# sheet1.net
KiCad netlist of a schematic drawn in Altium Designer
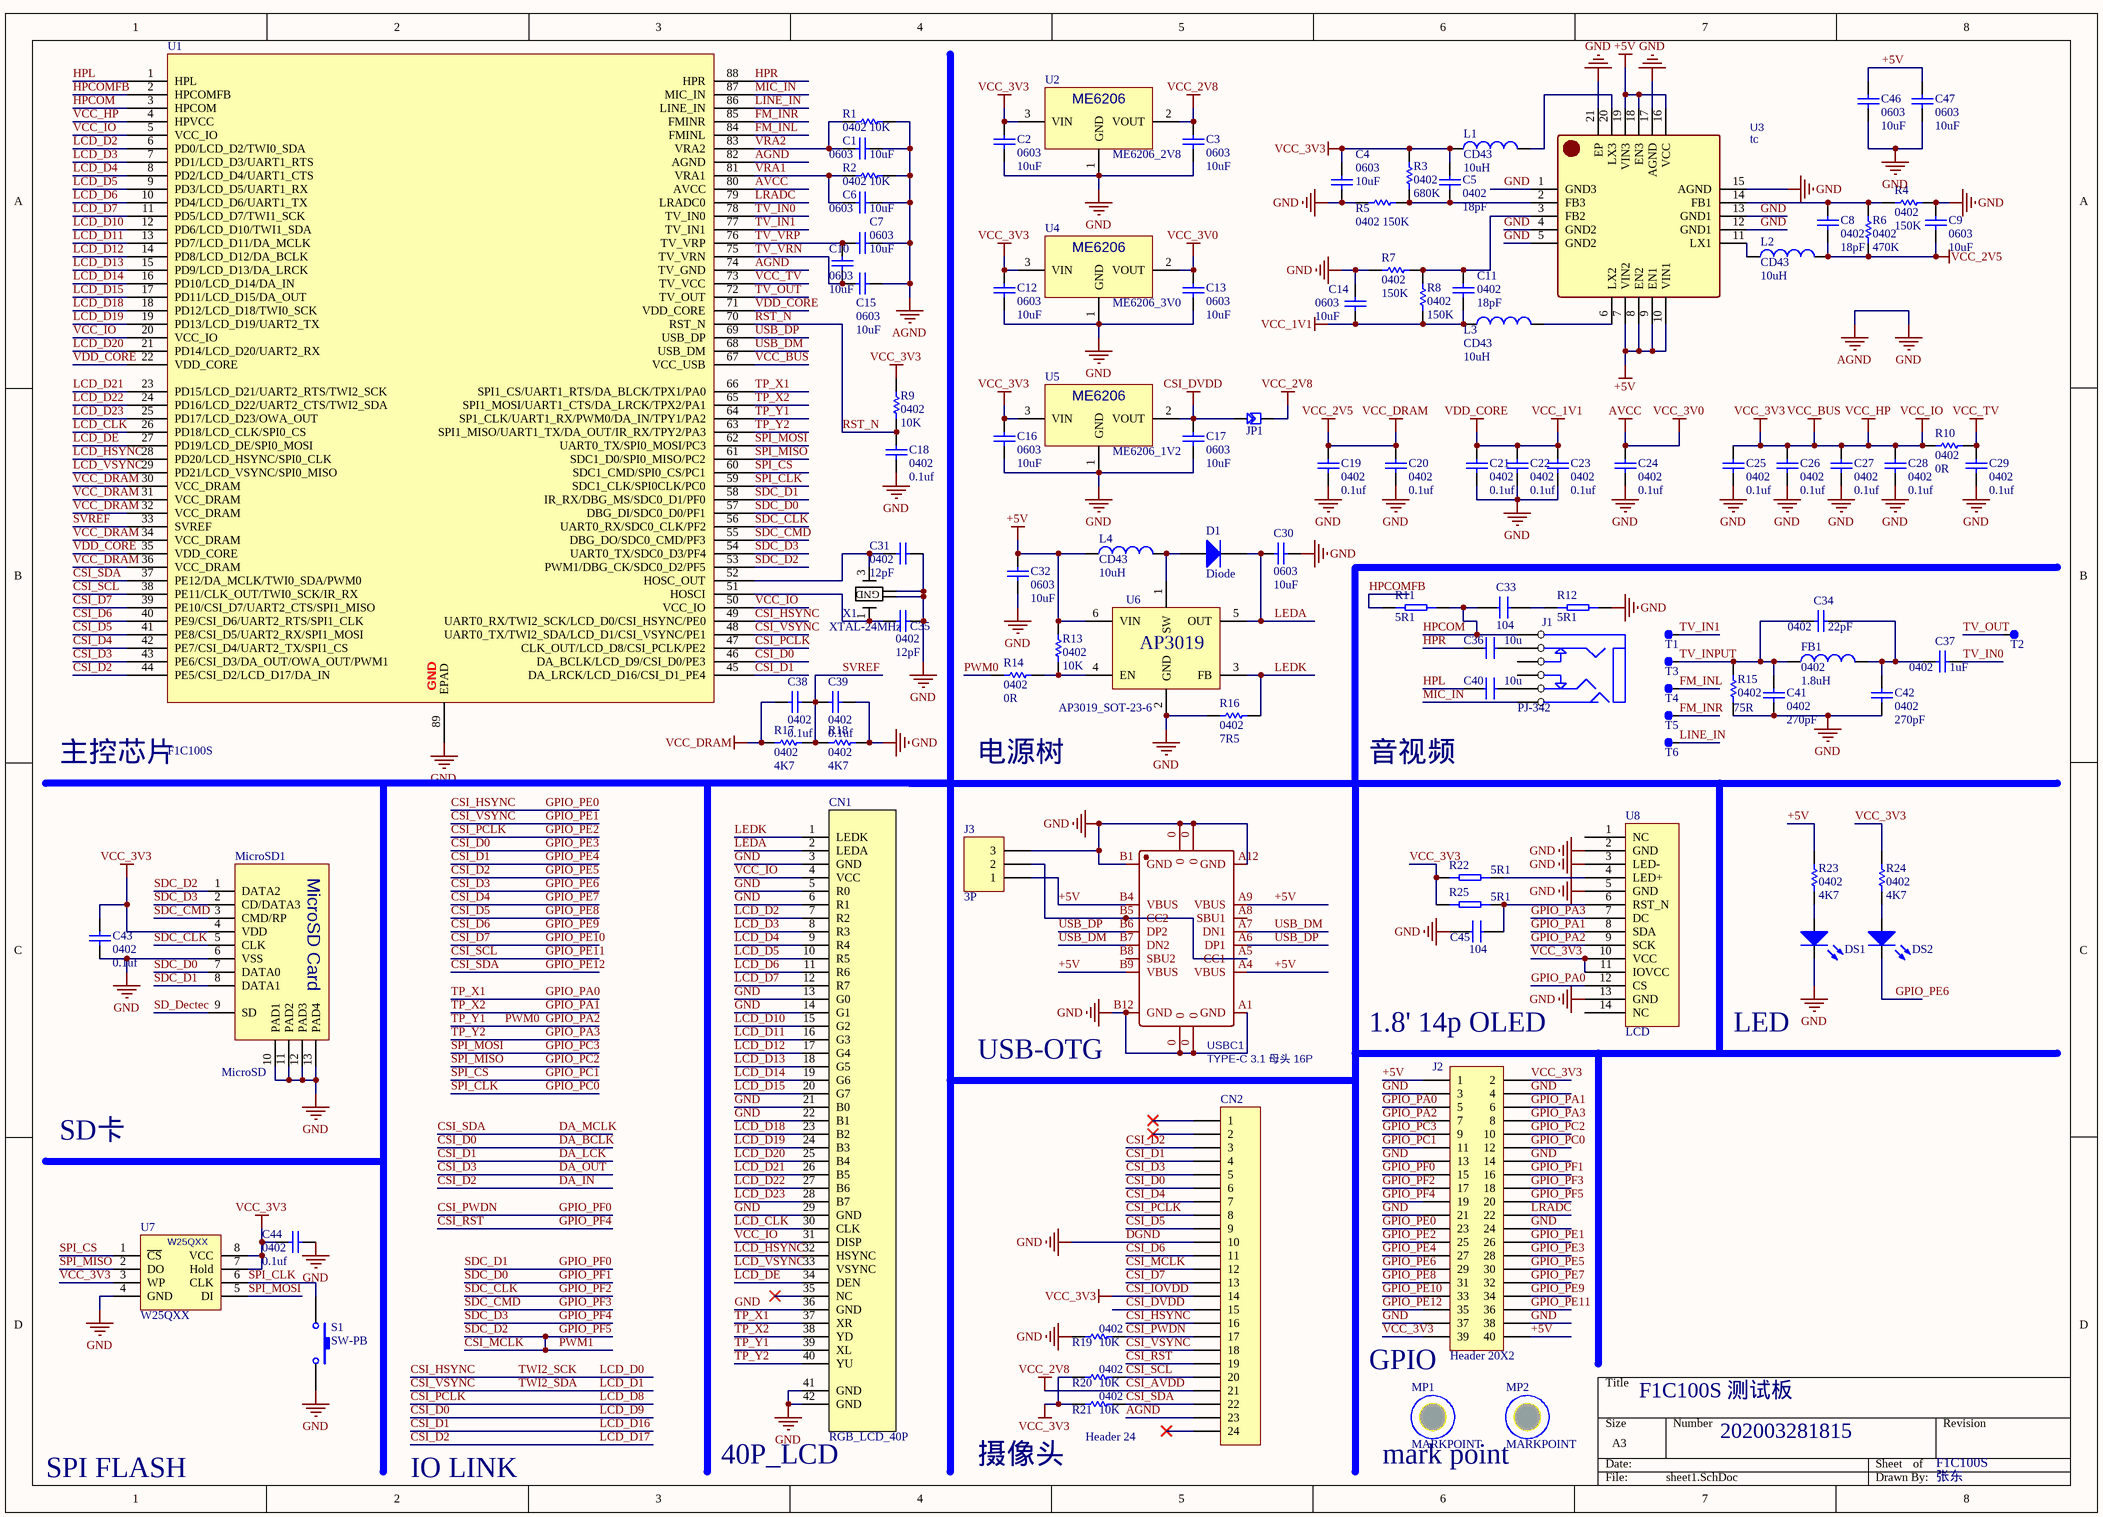
[diagram p0: sheet1.SchDoc]

(export (version "E")
  (design (tool "Eeschema 10.0.6"))
  (components
    (comp (ref "C1")
      (value "0603")
      (footprint "0603AC")
      (description "Capacitor")
      (fields (field (name "ALTIUM_VALUE") "10uF") (field (name "PUBLISHER") "Altium Limited"))
      (libsource (lib "Miscellaneous Devices") (part "Cap"))
    )
    (comp (ref "C2")
      (value "0603")
      (footprint "0603AC")
      (description "Capacitor")
      (fields (field (name "ALTIUM_VALUE") "10uF") (field (name "PUBLISHER") "Altium Limited"))
      (libsource (lib "Miscellaneous Devices") (part "Cap"))
    )
    (comp (ref "C3")
      (value "0603")
      (footprint "0603AC")
      (description "Capacitor")
      (fields (field (name "ALTIUM_VALUE") "10uF") (field (name "PUBLISHER") "Altium Limited"))
      (libsource (lib "Miscellaneous Devices") (part "Cap"))
    )
    (comp (ref "C4")
      (value "0603")
      (footprint "0603AC")
      (description "Capacitor")
      (fields (field (name "ALTIUM_VALUE") "10uF") (field (name "PUBLISHER") "Altium Limited"))
      (libsource (lib "Miscellaneous Devices") (part "Cap"))
    )
    (comp (ref "C5")
      (value "0402")
      (footprint "0402AC")
      (description "Capacitor")
      (fields (field (name "ALTIUM_VALUE") "18pF") (field (name "PUBLISHER") "Altium Limited"))
      (libsource (lib "Miscellaneous Devices") (part "Cap"))
    )
    (comp (ref "C6")
      (value "0603")
      (footprint "0603AC")
      (description "Capacitor")
      (fields (field (name "ALTIUM_VALUE") "10uF") (field (name "PUBLISHER") "Altium Limited"))
      (libsource (lib "Miscellaneous Devices") (part "Cap"))
    )
    (comp (ref "C7")
      (value "0603")
      (footprint "0603AC")
      (description "Capacitor")
      (fields (field (name "ALTIUM_VALUE") "10uF") (field (name "PUBLISHER") "Altium Limited"))
      (libsource (lib "Miscellaneous Devices") (part "Cap"))
    )
    (comp (ref "C8")
      (value "0402")
      (footprint "0402AC")
      (description "Capacitor")
      (fields (field (name "ALTIUM_VALUE") "18pF") (field (name "PUBLISHER") "Altium Limited"))
      (libsource (lib "Miscellaneous Devices") (part "Cap"))
    )
    (comp (ref "C9")
      (value "0603")
      (footprint "0603AC")
      (description "Capacitor")
      (fields (field (name "ALTIUM_VALUE") "10uF") (field (name "PUBLISHER") "Altium Limited"))
      (libsource (lib "Miscellaneous Devices") (part "Cap"))
    )
    (comp (ref "C10")
      (value "0603")
      (footprint "0603AC")
      (description "Capacitor")
      (fields (field (name "ALTIUM_VALUE") "10uF") (field (name "PUBLISHER") "Altium Limited"))
      (libsource (lib "Miscellaneous Devices") (part "Cap"))
    )
    (comp (ref "C11")
      (value "0402")
      (footprint "0402AC")
      (description "Capacitor")
      (fields (field (name "ALTIUM_VALUE") "18pF") (field (name "PUBLISHER") "Altium Limited"))
      (libsource (lib "Miscellaneous Devices") (part "Cap"))
    )
    (comp (ref "C12")
      (value "0603")
      (footprint "0603AC")
      (description "Capacitor")
      (fields (field (name "ALTIUM_VALUE") "10uF") (field (name "PUBLISHER") "Altium Limited"))
      (libsource (lib "Miscellaneous Devices") (part "Cap"))
    )
    (comp (ref "C13")
      (value "0603")
      (footprint "0603AC")
      (description "Capacitor")
      (fields (field (name "ALTIUM_VALUE") "10uF") (field (name "PUBLISHER") "Altium Limited"))
      (libsource (lib "Miscellaneous Devices") (part "Cap"))
    )
    (comp (ref "C14")
      (value "0603")
      (footprint "0603AC")
      (description "Capacitor")
      (fields (field (name "ALTIUM_VALUE") "10uF") (field (name "PUBLISHER") "Altium Limited"))
      (libsource (lib "Miscellaneous Devices") (part "Cap"))
    )
    (comp (ref "C15")
      (value "0603")
      (footprint "0603AC")
      (description "Capacitor")
      (fields (field (name "ALTIUM_VALUE") "10uF") (field (name "PUBLISHER") "Altium Limited"))
      (libsource (lib "Miscellaneous Devices") (part "Cap"))
    )
    (comp (ref "C16")
      (value "0603")
      (footprint "0603AC")
      (description "Capacitor")
      (fields (field (name "ALTIUM_VALUE") "10uF") (field (name "PUBLISHER") "Altium Limited"))
      (libsource (lib "Miscellaneous Devices") (part "Cap"))
    )
    (comp (ref "C17")
      (value "0603")
      (footprint "0603AC")
      (description "Capacitor")
      (fields (field (name "ALTIUM_VALUE") "10uF") (field (name "PUBLISHER") "Altium Limited"))
      (libsource (lib "Miscellaneous Devices") (part "Cap"))
    )
    (comp (ref "C18")
      (value "0402")
      (footprint "0402AC")
      (description "Capacitor")
      (fields (field (name "ALTIUM_VALUE") "0.1uf") (field (name "PUBLISHER") "Altium Limited"))
      (libsource (lib "Miscellaneous Devices") (part "Cap"))
    )
    (comp (ref "C19")
      (value "0402")
      (footprint "0402AC")
      (description "Capacitor")
      (fields (field (name "ALTIUM_VALUE") "0.1uf") (field (name "PUBLISHER") "Altium Limited"))
      (libsource (lib "Miscellaneous Devices") (part "Cap"))
    )
    (comp (ref "C20")
      (value "0402")
      (footprint "0402AC")
      (description "Capacitor")
      (fields (field (name "ALTIUM_VALUE") "0.1uf") (field (name "PUBLISHER") "Altium Limited"))
      (libsource (lib "Miscellaneous Devices") (part "Cap"))
    )
    (comp (ref "C21")
      (value "0402")
      (footprint "0402AC")
      (description "Capacitor")
      (fields (field (name "ALTIUM_VALUE") "0.1uf") (field (name "PUBLISHER") "Altium Limited"))
      (libsource (lib "Miscellaneous Devices") (part "Cap"))
    )
    (comp (ref "C22")
      (value "0402")
      (footprint "0402AC")
      (description "Capacitor")
      (fields (field (name "ALTIUM_VALUE") "0.1uf") (field (name "PUBLISHER") "Altium Limited"))
      (libsource (lib "Miscellaneous Devices") (part "Cap"))
    )
    (comp (ref "C23")
      (value "0402")
      (footprint "0402AC")
      (description "Capacitor")
      (fields (field (name "ALTIUM_VALUE") "0.1uf") (field (name "PUBLISHER") "Altium Limited"))
      (libsource (lib "Miscellaneous Devices") (part "Cap"))
    )
    (comp (ref "C24")
      (value "0402")
      (footprint "0402AC")
      (description "Capacitor")
      (fields (field (name "ALTIUM_VALUE") "0.1uf") (field (name "PUBLISHER") "Altium Limited"))
      (libsource (lib "Miscellaneous Devices") (part "Cap"))
    )
    (comp (ref "C25")
      (value "0402")
      (footprint "0402AC")
      (description "Capacitor")
      (fields (field (name "ALTIUM_VALUE") "0.1uf") (field (name "PUBLISHER") "Altium Limited"))
      (libsource (lib "Miscellaneous Devices") (part "Cap"))
    )
    (comp (ref "C26")
      (value "0402")
      (footprint "0402AC")
      (description "Capacitor")
      (fields (field (name "ALTIUM_VALUE") "0.1uf") (field (name "PUBLISHER") "Altium Limited"))
      (libsource (lib "Miscellaneous Devices") (part "Cap"))
    )
    (comp (ref "C27")
      (value "0402")
      (footprint "0402AC")
      (description "Capacitor")
      (fields (field (name "ALTIUM_VALUE") "0.1uf") (field (name "PUBLISHER") "Altium Limited"))
      (libsource (lib "Miscellaneous Devices") (part "Cap"))
    )
    (comp (ref "C28")
      (value "0402")
      (footprint "0402AC")
      (description "Capacitor")
      (fields (field (name "ALTIUM_VALUE") "0.1uf") (field (name "PUBLISHER") "Altium Limited"))
      (libsource (lib "Miscellaneous Devices") (part "Cap"))
    )
    (comp (ref "C29")
      (value "0402")
      (footprint "0402AC")
      (description "Capacitor")
      (fields (field (name "ALTIUM_VALUE") "0.1uf") (field (name "PUBLISHER") "Altium Limited"))
      (libsource (lib "Miscellaneous Devices") (part "Cap"))
    )
    (comp (ref "C30")
      (value "0603")
      (footprint "0603AC")
      (description "Capacitor")
      (fields (field (name "ALTIUM_VALUE") "10uF") (field (name "PUBLISHER") "Altium Limited"))
      (libsource (lib "Miscellaneous Devices") (part "Cap"))
    )
    (comp (ref "C31")
      (value "0402")
      (footprint "0402AC")
      (description "Capacitor")
      (fields (field (name "ALTIUM_VALUE") "12pF") (field (name "PUBLISHER") "Altium Limited"))
      (libsource (lib "Miscellaneous Devices") (part "Cap"))
    )
    (comp (ref "C32")
      (value "0603")
      (footprint "0603AC")
      (description "Capacitor")
      (fields (field (name "ALTIUM_VALUE") "10uF") (field (name "PUBLISHER") "Altium Limited"))
      (libsource (lib "Miscellaneous Devices") (part "Cap"))
    )
    (comp (ref "C33")
      (value "104")
      (footprint "0402C")
      (description "SMD-CAP")
      (libsource (lib "lpi-nano-dock") (part "CAP"))
    )
    (comp (ref "C34")
      (value "0402")
      (footprint "0402AC")
      (description "Capacitor")
      (fields (field (name "ALTIUM_VALUE") "22pF") (field (name "PUBLISHER") "Altium Limited"))
      (libsource (lib "Miscellaneous Devices") (part "Cap"))
    )
    (comp (ref "C35")
      (value "0402")
      (footprint "0402AC")
      (description "Capacitor")
      (fields (field (name "ALTIUM_VALUE") "12pF") (field (name "PUBLISHER") "Altium Limited"))
      (libsource (lib "Miscellaneous Devices") (part "Cap"))
    )
    (comp (ref "C36")
      (value "10u")
      (footprint "0402C")
      (description "SMD-CAP")
      (libsource (lib "lpi-nano-dock") (part "CAP"))
    )
    (comp (ref "C37")
      (value "0402")
      (footprint "0402AC")
      (description "Capacitor")
      (fields (field (name "ALTIUM_VALUE") "1uF") (field (name "PUBLISHER") "Altium Limited"))
      (libsource (lib "Miscellaneous Devices") (part "Cap"))
    )
    (comp (ref "C38")
      (value "0402")
      (footprint "0402AC")
      (description "Capacitor")
      (fields (field (name "ALTIUM_VALUE") "0.1uf") (field (name "PUBLISHER") "Altium Limited"))
      (libsource (lib "Miscellaneous Devices") (part "Cap"))
    )
    (comp (ref "C39")
      (value "0402")
      (footprint "0402AC")
      (description "Capacitor")
      (fields (field (name "ALTIUM_VALUE") "0.1uf") (field (name "PUBLISHER") "Altium Limited"))
      (libsource (lib "Miscellaneous Devices") (part "Cap"))
    )
    (comp (ref "C40")
      (value "10u")
      (footprint "0402C")
      (description "SMD-CAP")
      (libsource (lib "lpi-nano-dock") (part "CAP"))
    )
    (comp (ref "C41")
      (value "0402")
      (footprint "0402AC")
      (description "Capacitor")
      (fields (field (name "ALTIUM_VALUE") "270pF") (field (name "PUBLISHER") "Altium Limited"))
      (libsource (lib "Miscellaneous Devices") (part "Cap"))
    )
    (comp (ref "C42")
      (value "0402")
      (footprint "0402AC")
      (description "Capacitor")
      (fields (field (name "ALTIUM_VALUE") "270pF") (field (name "PUBLISHER") "Altium Limited"))
      (libsource (lib "Miscellaneous Devices") (part "Cap"))
    )
    (comp (ref "C43")
      (value "0402")
      (footprint "0402AC")
      (description "Capacitor")
      (fields (field (name "ALTIUM_VALUE") "0.1uf") (field (name "PUBLISHER") "Altium Limited"))
      (libsource (lib "Miscellaneous Devices") (part "Cap"))
    )
    (comp (ref "C44")
      (value "0402")
      (footprint "0402AC")
      (description "Capacitor")
      (fields (field (name "ALTIUM_VALUE") "0.1uf") (field (name "PUBLISHER") "Altium Limited"))
      (libsource (lib "Miscellaneous Devices") (part "Cap"))
    )
    (comp (ref "C45")
      (value "104")
      (footprint "0402C")
      (description "SMD-CAP")
      (libsource (lib "lpi-nano-dock") (part "CAP"))
    )
    (comp (ref "C46")
      (value "0603")
      (footprint "0603AC")
      (description "Capacitor")
      (fields (field (name "ALTIUM_VALUE") "10uF") (field (name "PUBLISHER") "Altium Limited"))
      (libsource (lib "Miscellaneous Devices") (part "Cap"))
    )
    (comp (ref "C47")
      (value "0603")
      (footprint "0603AC")
      (description "Capacitor")
      (fields (field (name "ALTIUM_VALUE") "10uF") (field (name "PUBLISHER") "Altium Limited"))
      (libsource (lib "Miscellaneous Devices") (part "Cap"))
    )
    (comp (ref "CN1")
      (value "RGB_LCD_40P")
      (footprint "FH19C-40S-0.5SH")
      (libsource (lib "7426SCH") (part "RGB_LCD_40P"))
    )
    (comp (ref "CN2")
      (value "Header 24")
      (footprint "FH19C-24S-0.5SH")
      (description "Header, 24-Pin")
      (fields (field (name "PUBLISHER") "Altium Limited"))
      (libsource (lib "Miscellaneous Connectors") (part "Header 24"))
    )
    (comp (ref "D1")
      (value "Diode")
      (footprint "SOD123")
      (description "Default Diode")
      (fields (field (name "PUBLISHER") "Altium Limited"))
      (libsource (lib "Miscellaneous Devices") (part "Diode"))
    )
    (comp (ref "DS1") (value "LED") (footprint "LED 0805B") (libsource (lib "QT") (part "LED")))
    (comp (ref "DS2") (value "LED") (footprint "LED 0805B") (libsource (lib "QT") (part "LED")))
    (comp (ref "FB1")
      (value "0402")
      (footprint "0402AR")
      (description "CD43")
      (fields (field (name "ALTIUM_VALUE") "1.8uH") (field (name "PUBLISHER") "Altium Limited"))
      (libsource (lib "Miscellaneous Devices") (part "Inductor"))
    )
    (comp (ref "J1") (value "PJ-342") (footprint "PJ-342") (libsource (lib "lpi-nano-dock") (part "PJ-342")))
    (comp (ref "J2")
      (value "Header 20X2")
      (footprint "HDR2X20")
      (description "Header, 20-Pin, Dual row")
      (fields (field (name "PUBLISHER") "Altium Limited"))
      (libsource (lib "Miscellaneous Connectors") (part "Header 20X2"))
    )
    (comp (ref "J3") (value "3P") (footprint "3P") (libsource (lib "常用元件库") (part "3P")))
    (comp (ref "JP1") (value "SW-PAD-2") (footprint "SW-PAD-2") (libsource (lib "7426SCH") (part "SW-PAD-2")))
    (comp (ref "L1")
      (value "CD43")
      (footprint "2520")
      (fields (field (name "ALTIUM_VALUE") "10uH") (field (name "PUBLISHER") "Altium Limited"))
      (libsource (lib "Miscellaneous Devices") (part "Inductor"))
    )
    (comp (ref "L2")
      (value "CD43")
      (footprint "2520")
      (fields (field (name "ALTIUM_VALUE") "10uH") (field (name "PUBLISHER") "Altium Limited"))
      (libsource (lib "Miscellaneous Devices") (part "Inductor"))
    )
    (comp (ref "L3")
      (value "CD43")
      (footprint "2520")
      (fields (field (name "ALTIUM_VALUE") "10uH") (field (name "PUBLISHER") "Altium Limited"))
      (libsource (lib "Miscellaneous Devices") (part "Inductor"))
    )
    (comp (ref "L4")
      (value "CD43")
      (footprint "2520")
      (fields (field (name "ALTIUM_VALUE") "10uH") (field (name "PUBLISHER") "Altium Limited"))
      (libsource (lib "Miscellaneous Devices") (part "Inductor"))
    )
    (comp (ref "MicroSD1")
      (value "MicroSD")
      (footprint "MicroSD")
      (libsource (lib "7426SCH") (part "MicroSD"))
    )
    (comp (ref "MP1")
      (value "MARKPOINT")
      (footprint "MARKPOINT")
      (libsource (lib "7426SCH") (part "MARKPOINT"))
    )
    (comp (ref "MP2")
      (value "MARKPOINT")
      (footprint "MARKPOINT")
      (libsource (lib "7426SCH") (part "MARKPOINT"))
    )
    (comp (ref "R1")
      (value "0402")
      (footprint "0402AR")
      (description "Resistor")
      (fields (field (name "ALTIUM_VALUE") "10K") (field (name "PUBLISHER") "Altium Limited"))
      (libsource (lib "Miscellaneous Devices") (part "Res1"))
    )
    (comp (ref "R2")
      (value "0402")
      (footprint "0402AR")
      (description "Resistor")
      (fields (field (name "ALTIUM_VALUE") "10K") (field (name "PUBLISHER") "Altium Limited"))
      (libsource (lib "Miscellaneous Devices") (part "Res1"))
    )
    (comp (ref "R3")
      (value "0402")
      (footprint "0402AR")
      (fields (field (name "ALTIUM_VALUE") "680K") (field (name "PUBLISHER") "Altium Limited"))
      (libsource (lib "Miscellaneous Devices") (part "Res1"))
    )
    (comp (ref "R4")
      (value "0402")
      (footprint "0402AR")
      (description "Resistor")
      (fields (field (name "ALTIUM_VALUE") "150K") (field (name "PUBLISHER") "Altium Limited"))
      (libsource (lib "Miscellaneous Devices") (part "Res1"))
    )
    (comp (ref "R5")
      (value "0402")
      (footprint "0402AR")
      (description "Resistor")
      (fields (field (name "ALTIUM_VALUE") "150K") (field (name "PUBLISHER") "Altium Limited"))
      (libsource (lib "Miscellaneous Devices") (part "Res1"))
    )
    (comp (ref "R6")
      (value "0402")
      (footprint "0402AR")
      (fields (field (name "ALTIUM_VALUE") "470K") (field (name "PUBLISHER") "Altium Limited"))
      (libsource (lib "Miscellaneous Devices") (part "Res1"))
    )
    (comp (ref "R7")
      (value "0402")
      (footprint "0402AR")
      (fields (field (name "ALTIUM_VALUE") "150K") (field (name "PUBLISHER") "Altium Limited"))
      (libsource (lib "Miscellaneous Devices") (part "Res1"))
    )
    (comp (ref "R8")
      (value "0402")
      (footprint "0402AR")
      (fields (field (name "ALTIUM_VALUE") "150K") (field (name "PUBLISHER") "Altium Limited"))
      (libsource (lib "Miscellaneous Devices") (part "Res1"))
    )
    (comp (ref "R9")
      (value "0402")
      (footprint "0402AR")
      (fields (field (name "ALTIUM_VALUE") "10K") (field (name "PUBLISHER") "Altium Limited"))
      (libsource (lib "Miscellaneous Devices") (part "Res1"))
    )
    (comp (ref "R10")
      (value "0402")
      (footprint "0402AR")
      (fields (field (name "ALTIUM_VALUE") "0R") (field (name "PUBLISHER") "Altium Limited"))
      (libsource (lib "Miscellaneous Devices") (part "Res1"))
    )
    (comp (ref "R11") (value "5R1") (footprint "0402R") (libsource (lib "lpi-nano-dock") (part "R")))
    (comp (ref "R12") (value "5R1") (footprint "0402R") (libsource (lib "lpi-nano-dock") (part "R")))
    (comp (ref "R13")
      (value "0402")
      (footprint "0402AR")
      (fields (field (name "ALTIUM_VALUE") "10K") (field (name "PUBLISHER") "Altium Limited"))
      (libsource (lib "Miscellaneous Devices") (part "Res1"))
    )
    (comp (ref "R14")
      (value "0402")
      (footprint "0402AR")
      (fields (field (name "ALTIUM_VALUE") "0R") (field (name "PUBLISHER") "Altium Limited"))
      (libsource (lib "Miscellaneous Devices") (part "Res1"))
    )
    (comp (ref "R15")
      (value "0402")
      (footprint "0402AR")
      (description "Resistor")
      (fields (field (name "ALTIUM_VALUE") "75R") (field (name "PUBLISHER") "Altium Limited"))
      (libsource (lib "Miscellaneous Devices") (part "Res1"))
    )
    (comp (ref "R16")
      (value "0402")
      (footprint "0402AR")
      (fields (field (name "ALTIUM_VALUE") "7R5") (field (name "PUBLISHER") "Altium Limited"))
      (libsource (lib "Miscellaneous Devices") (part "Res1"))
    )
    (comp (ref "R17")
      (value "0402")
      (footprint "0402AR")
      (fields (field (name "ALTIUM_VALUE") "4K7") (field (name "PUBLISHER") "Altium Limited"))
      (libsource (lib "Miscellaneous Devices") (part "Res1"))
    )
    (comp (ref "R18")
      (value "0402")
      (footprint "0402AR")
      (fields (field (name "ALTIUM_VALUE") "4K7") (field (name "PUBLISHER") "Altium Limited"))
      (libsource (lib "Miscellaneous Devices") (part "Res1"))
    )
    (comp (ref "R19")
      (value "0402")
      (footprint "0402AR")
      (fields (field (name "ALTIUM_VALUE") "10K") (field (name "PUBLISHER") "Altium Limited"))
      (libsource (lib "Miscellaneous Devices") (part "Res1"))
    )
    (comp (ref "R20")
      (value "0402")
      (footprint "0402AR")
      (fields (field (name "ALTIUM_VALUE") "10K") (field (name "PUBLISHER") "Altium Limited"))
      (libsource (lib "Miscellaneous Devices") (part "Res1"))
    )
    (comp (ref "R21")
      (value "0402")
      (footprint "0402AR")
      (fields (field (name "ALTIUM_VALUE") "10K") (field (name "PUBLISHER") "Altium Limited"))
      (libsource (lib "Miscellaneous Devices") (part "Res1"))
    )
    (comp (ref "R22") (value "5R1") (footprint "0402R") (libsource (lib "lpi-nano-dock") (part "R")))
    (comp (ref "R23")
      (value "0402")
      (footprint "0402AR")
      (fields (field (name "ALTIUM_VALUE") "4K7") (field (name "PUBLISHER") "Altium Limited"))
      (libsource (lib "PineapplePi-F1") (part "Res1"))
    )
    (comp (ref "R24")
      (value "0402")
      (footprint "0402AR")
      (fields (field (name "ALTIUM_VALUE") "4K7") (field (name "PUBLISHER") "Altium Limited"))
      (libsource (lib "PineapplePi-F1") (part "Res1"))
    )
    (comp (ref "R25") (value "5R1") (footprint "0402R") (libsource (lib "lpi-nano-dock") (part "R")))
    (comp (ref "S1")
      (value "SW-PB")
      (footprint "SW-SMD1")
      (description "Switch")
      (fields (field (name "PUBLISHER") "Altium Limited"))
      (libsource (lib "Miscellaneous Devices") (part "SW-PB"))
    )
    (comp (ref "T1") (value "1 测试点") (footprint "SIP1-1*1") (libsource (lib "常用元件库") (part "1 测试点")))
    (comp (ref "T2") (value "1 测试点") (footprint "SIP1-1*1") (libsource (lib "常用元件库") (part "1 测试点")))
    (comp (ref "T3") (value "1 测试点") (footprint "SIP1-1*1") (libsource (lib "常用元件库") (part "1 测试点")))
    (comp (ref "T4") (value "1 测试点") (footprint "SIP1-1*1") (libsource (lib "常用元件库") (part "1 测试点")))
    (comp (ref "T5") (value "1 测试点") (footprint "SIP1-1*1") (libsource (lib "常用元件库") (part "1 测试点")))
    (comp (ref "T6") (value "1 测试点") (footprint "SIP1-1*1") (libsource (lib "常用元件库") (part "1 测试点")))
    (comp (ref "U1") (value "F1C100S") (footprint "QFN88-10X10") (libsource (lib "F1C100S") (part "F1C100S")))
    (comp (ref "U2") (value "ME6206_2V8") (footprint "SOT-23") (libsource (lib "IC") (part "ME6206")))
    (comp (ref "U3")
      (value "tc")
      (footprint "QFN20-3x3-0.4")
      (fields (field (name "BOM_MANUFACTURER PART") "EA3036QDR") (field (name "BOM_SUPPLIER PART") "C111587"))
      (libsource (lib "IC") (part "EA3036QDR"))
    )
    (comp (ref "U4") (value "ME6206_3V0") (footprint "SOT-23") (libsource (lib "IC") (part "ME6206")))
    (comp (ref "U5") (value "ME6206_1V2") (footprint "SOT-23") (libsource (lib "IC") (part "ME6206")))
    (comp (ref "U6") (value "AP3019_SOT-23-6") (footprint "SOT23-6") (libsource (lib "IC") (part "AP3019")))
    (comp (ref "U7") (value "W25QXX") (footprint "SO-8M") (libsource (lib "IC") (part "W25QXX")))
    (comp (ref "U8")
      (value "LCD")
      (footprint "LCD_SPI_14P_sim")
      (libsource (lib "lpi-nano-dock") (part "LCD_SPI_14P"))
    )
    (comp (ref "USBC1")
      (value "TYPE-C 3.1 母头 16P")
      (footprint "TYPE-C-USB-12")
      (libsource (lib "Interface") (part "TYPE-C 3.1 母头 16P"))
    )
    (comp (ref "X1")
      (value "XTAL-24MHz")
      (footprint "XTAL-3225")
      (libsource (lib "7426SCH") (part "XTAL-SMD"))
    )
  )
  (nets
    (net (code "1") (name "+5V") (class "Default")
      (node (ref "C32") (pin "2") (pinfunction "2_2") (pintype "passive"))
      (node (ref "C46") (pin "2") (pinfunction "2_2") (pintype "passive"))
      (node (ref "C47") (pin "2") (pinfunction "2_2") (pintype "passive"))
      (node (ref "J2") (pin "1") (pinfunction "1_1") (pintype "passive"))
      (node (ref "J2") (pin "40") (pinfunction "40_40") (pintype "passive"))
      (node (ref "J3") (pin "1") (pinfunction "1_1") (pintype "passive"))
      (node (ref "L4") (pin "1") (pinfunction "1_1") (pintype "passive"))
      (node (ref "R13") (pin "1") (pinfunction "1_1") (pintype "passive"))
      (node (ref "R23") (pin "2") (pinfunction "2_2") (pintype "passive"))
      (node (ref "U3") (pin "10") (pinfunction "VIN1_10") (pintype "passive"))
      (node (ref "U3") (pin "16") (pinfunction "VCC_16") (pintype "passive"))
      (node (ref "U3") (pin "18") (pinfunction "EN3_18") (pintype "passive"))
      (node (ref "U3") (pin "19") (pinfunction "VIN3_19") (pintype "passive"))
      (node (ref "U3") (pin "7") (pinfunction "VIN2_7") (pintype "passive"))
      (node (ref "U3") (pin "8") (pinfunction "EN2_8") (pintype "passive"))
      (node (ref "U3") (pin "9") (pinfunction "EN1_9") (pintype "passive"))
      (node (ref "U6") (pin "6") (pinfunction "VIN_6") (pintype "passive"))
      (node (ref "USBC1") (pin "A4") (pinfunction "VBUS_A4") (pintype "passive"))
      (node (ref "USBC1") (pin "A9") (pinfunction "VBUS_A9") (pintype "passive"))
      (node (ref "USBC1") (pin "B4") (pinfunction "VBUS_B4") (pintype "passive"))
      (node (ref "USBC1") (pin "B9") (pinfunction "VBUS_B9") (pintype "passive"))
    )
    (net (code "2") (name "/CSI_D0") (class "Default")
      (node (ref "CN2") (pin "6") (pinfunction "6_6") (pintype "passive"))
      (node (ref "J2") (pin "28") (pinfunction "28_28") (pintype "passive"))
      (node (ref "U1") (pin "46") (pinfunction "DA_BCLK/LCD_D9/CSI_D0/PE3_46") (pintype "passive"))
    )
    (net (code "3") (name "/CSI_D1") (class "Default")
      (node (ref "CN2") (pin "4") (pinfunction "4_4") (pintype "passive"))
      (node (ref "J2") (pin "27") (pinfunction "27_27") (pintype "passive"))
      (node (ref "U1") (pin "45") (pinfunction "DA_LRCK/LCD_D16/CSI_D1_PE4_45") (pintype "passive"))
    )
    (net (code "4") (name "/CSI_D2") (class "Default")
      (node (ref "CN2") (pin "3") (pinfunction "3_3") (pintype "passive"))
      (node (ref "J2") (pin "30") (pinfunction "30_30") (pintype "passive"))
      (node (ref "U1") (pin "44") (pinfunction "PE5/CSI_D2/LCD_D17/DA_IN_44") (pintype "passive"))
    )
    (net (code "5") (name "/CSI_D3") (class "Default")
      (node (ref "CN2") (pin "5") (pinfunction "5_5") (pintype "passive"))
      (node (ref "DS2") (pin "2") (pinfunction "K_2") (pintype "passive"))
      (node (ref "J2") (pin "29") (pinfunction "29_29") (pintype "passive"))
      (node (ref "U1") (pin "43") (pinfunction "PE6/CSI_D3/DA_OUT/OWA_OUT/PWM1_43") (pintype "passive"))
    )
    (net (code "6") (name "/CSI_D4") (class "Default")
      (node (ref "CN2") (pin "7") (pinfunction "7_7") (pintype "passive"))
      (node (ref "J2") (pin "32") (pinfunction "32_32") (pintype "passive"))
      (node (ref "U1") (pin "42") (pinfunction "PE7/CSI_D4/UART2_TX/SPI1_CS_42") (pintype "passive"))
    )
    (net (code "7") (name "/CSI_D5") (class "Default")
      (node (ref "CN2") (pin "9") (pinfunction "9_9") (pintype "passive"))
      (node (ref "J2") (pin "31") (pinfunction "31_31") (pintype "passive"))
      (node (ref "U1") (pin "41") (pinfunction "PE8/CSI_D5/UART2_RX/SPI1_MOSI_41") (pintype "passive"))
    )
    (net (code "8") (name "/CSI_D6") (class "Default")
      (node (ref "CN2") (pin "11") (pinfunction "11_11") (pintype "passive"))
      (node (ref "J2") (pin "34") (pinfunction "34_34") (pintype "passive"))
      (node (ref "U1") (pin "40") (pinfunction "PE9/CSI_D6/UART2_RTS/SPI1_CLK_40") (pintype "passive"))
    )
    (net (code "9") (name "/CSI_D7") (class "Default")
      (node (ref "CN2") (pin "13") (pinfunction "13_13") (pintype "passive"))
      (node (ref "J2") (pin "33") (pinfunction "33_33") (pintype "passive"))
      (node (ref "U1") (pin "39") (pinfunction "PE10/CSI_D7/UART2_CTS/SPI1_MISO_39") (pintype "passive"))
    )
    (net (code "10") (name "/CSI_HSYNC") (class "Default")
      (node (ref "CN2") (pin "16") (pinfunction "16_16") (pintype "passive"))
      (node (ref "J2") (pin "23") (pinfunction "23_23") (pintype "passive"))
      (node (ref "U1") (pin "49") (pinfunction "UART0_RX/TWI2_SCK/LCD_D0/CSI_HSYNC/PE0_49") (pintype "passive"))
    )
    (net (code "11") (name "/CSI_MCLK") (class "Default")
      (node (ref "CN2") (pin "12") (pinfunction "12_12") (pintype "passive"))
      (node (ref "J2") (pin "20") (pinfunction "20_20") (pintype "passive"))
      (node (ref "MicroSD1") (pin "1") (pinfunction "DATA2_1") (pintype "power_in"))
      (node (ref "U1") (pin "53") (pinfunction "PWM1/DBG_CK/SDC0_D2/PF5_53") (pintype "passive"))
    )
    (net (code "12") (name "/CSI_PCLK") (class "Default")
      (node (ref "CN2") (pin "8") (pinfunction "8_8") (pintype "passive"))
      (node (ref "J2") (pin "25") (pinfunction "25_25") (pintype "passive"))
      (node (ref "U1") (pin "47") (pinfunction "CLK_OUT/LCD_D8/CSI_PCLK/PE2_47") (pintype "passive"))
    )
    (net (code "13") (name "/CSI_PWDN") (class "Default")
      (node (ref "CN2") (pin "17") (pinfunction "17_17") (pintype "passive"))
      (node (ref "J2") (pin "15") (pinfunction "15_15") (pintype "passive"))
      (node (ref "MicroSD1") (pin "8") (pinfunction "DATA1_8") (pintype "power_in"))
      (node (ref "R19") (pin "2") (pinfunction "2_2") (pintype "passive"))
      (node (ref "U1") (pin "58") (pinfunction "IR_RX/DBG_MS/SDC0_D1/PF0_58") (pintype "passive"))
    )
    (net (code "14") (name "/CSI_RST") (class "Default")
      (node (ref "CN2") (pin "19") (pinfunction "19_19") (pintype "passive"))
      (node (ref "J2") (pin "19") (pinfunction "19_19") (pintype "passive"))
      (node (ref "MicroSD1") (pin "2") (pinfunction "CD/DATA3_2") (pintype "power_in"))
      (node (ref "U1") (pin "54") (pinfunction "UART0_TX/SDC0_D3/PF4_54") (pintype "passive"))
    )
    (net (code "15") (name "/CSI_SCL") (class "Default")
      (node (ref "CN2") (pin "20") (pinfunction "20_20") (pintype "passive"))
      (node (ref "J2") (pin "36") (pinfunction "36_36") (pintype "passive"))
      (node (ref "R20") (pin "1") (pinfunction "1_1") (pintype "passive"))
      (node (ref "U1") (pin "38") (pinfunction "PE11/CLK_OUT/TWI0_SCK/IR_RX_38") (pintype "passive"))
    )
    (net (code "16") (name "/CSI_SDA") (class "Default")
      (node (ref "CN2") (pin "22") (pinfunction "22_22") (pintype "passive"))
      (node (ref "J2") (pin "35") (pinfunction "35_35") (pintype "passive"))
      (node (ref "R21") (pin "1") (pinfunction "1_1") (pintype "passive"))
      (node (ref "U1") (pin "37") (pinfunction "PE12/DA_MCLK/TWI0_SDA/PWM0_37") (pintype "passive"))
    )
    (net (code "17") (name "/CSI_VSYNC") (class "Default")
      (node (ref "CN2") (pin "18") (pinfunction "18_18") (pintype "passive"))
      (node (ref "J2") (pin "26") (pinfunction "26_26") (pintype "passive"))
      (node (ref "U1") (pin "48") (pinfunction "UART0_TX/TWI2_SDA/LCD_D1/CSI_VSYNC/PE1_48") (pintype "passive"))
    )
    (net (code "18") (name "/FM_INL") (class "Default")
      (node (ref "T4") (pin "1") (pintype "passive"))
      (node (ref "U1") (pin "84") (pinfunction "FMINL_84") (pintype "passive"))
    )
    (net (code "19") (name "/FM_INR") (class "Default")
      (node (ref "T5") (pin "1") (pintype "passive"))
      (node (ref "U1") (pin "85") (pinfunction "FMINR_85") (pintype "passive"))
    )
    (net (code "20") (name "/GPIO_PA0") (class "Default")
      (node (ref "CN1") (pin "37") (pinfunction "XR_37") (pintype "passive"))
      (node (ref "J2") (pin "5") (pinfunction "5_5") (pintype "passive"))
      (node (ref "U1") (pin "66") (pinfunction "SPI1_CS/UART1_RTS/DA_BLCK/TPX1/PA0_66") (pintype "passive"))
      (node (ref "U8") (pin "12") (pinfunction "CS_12") (pintype "passive"))
    )
    (net (code "21") (name "/GPIO_PA1") (class "Default")
      (node (ref "CN1") (pin "38") (pinfunction "YD_38") (pintype "passive"))
      (node (ref "J2") (pin "6") (pinfunction "6_6") (pintype "passive"))
      (node (ref "U1") (pin "65") (pinfunction "SPI1_MOSI/UART1_CTS/DA_LRCK/TPX2/PA1_65") (pintype "passive"))
      (node (ref "U8") (pin "8") (pinfunction "SDA_8") (pintype "passive"))
    )
    (net (code "22") (name "/GPIO_PA2") (class "Default")
      (node (ref "CN1") (pin "39") (pinfunction "XL_39") (pintype "passive"))
      (node (ref "J2") (pin "7") (pinfunction "7_7") (pintype "passive"))
      (node (ref "R14") (pin "1") (pinfunction "1_1") (pintype "passive"))
      (node (ref "U1") (pin "64") (pinfunction "SP1_CLK/UART1_RX/PWM0/DA_IN/TPY1/PA2_64") (pintype "passive"))
      (node (ref "U8") (pin "9") (pinfunction "SCK_9") (pintype "passive"))
    )
    (net (code "23") (name "/GPIO_PA3") (class "Default")
      (node (ref "CN1") (pin "40") (pinfunction "YU_40") (pintype "passive"))
      (node (ref "J2") (pin "8") (pinfunction "8_8") (pintype "passive"))
      (node (ref "U1") (pin "63") (pinfunction "SPI1_MISO/UART1_TX/DA_OUT/IR_RX/TPY2/PA3_63") (pintype "passive"))
      (node (ref "U8") (pin "7") (pinfunction "DC_7") (pintype "passive"))
    )
    (net (code "24") (name "/GPIO_PC0") (class "Default")
      (node (ref "J2") (pin "12") (pinfunction "12_12") (pintype "passive"))
      (node (ref "S1") (pin "1") (pinfunction "1_1") (pintype "passive"))
      (node (ref "U1") (pin "59") (pinfunction "SDC1_CLK/SPI0CLK/PC0_59") (pintype "passive"))
      (node (ref "U7") (pin "6") (pinfunction "CLK_6") (pintype "power_in"))
    )
    (net (code "25") (name "/GPIO_PC1") (class "Default")
      (node (ref "J2") (pin "11") (pinfunction "11_11") (pintype "passive"))
      (node (ref "U1") (pin "60") (pinfunction "SDC1_CMD/SPI0_CS/PC1_60") (pintype "passive"))
      (node (ref "U7") (pin "1") (pinfunction "~{CS}_1") (pintype "power_in"))
    )
    (net (code "26") (name "/GPIO_PC2") (class "Default")
      (node (ref "J2") (pin "10") (pinfunction "10_10") (pintype "passive"))
      (node (ref "U1") (pin "61") (pinfunction "SDC1_D0/SPI0_MISO/PC2_61") (pintype "passive"))
      (node (ref "U7") (pin "2") (pinfunction "DO_2") (pintype "power_in"))
    )
    (net (code "27") (name "/GPIO_PC3") (class "Default")
      (node (ref "J2") (pin "9") (pinfunction "9_9") (pintype "passive"))
      (node (ref "U1") (pin "62") (pinfunction "UART0_TX/SPI0_MOSI/PC3_62") (pintype "passive"))
      (node (ref "U7") (pin "5") (pinfunction "DI_5") (pintype "power_in"))
    )
    (net (code "28") (name "/GPIO_PF1") (class "Default")
      (node (ref "J2") (pin "16") (pinfunction "16_16") (pintype "passive"))
      (node (ref "MicroSD1") (pin "7") (pinfunction "DATA0_7") (pintype "power_in"))
      (node (ref "U1") (pin "57") (pinfunction "DBG_DI/SDC0_D0/PF1_57") (pintype "passive"))
    )
    (net (code "29") (name "/GPIO_PF2") (class "Default")
      (node (ref "J2") (pin "17") (pinfunction "17_17") (pintype "passive"))
      (node (ref "MicroSD1") (pin "5") (pinfunction "CLK_5") (pintype "power_in"))
      (node (ref "U1") (pin "56") (pinfunction "UART0_RX/SDC0_CLK/PF2_56") (pintype "passive"))
    )
    (net (code "30") (name "/GPIO_PF3") (class "Default")
      (node (ref "J2") (pin "18") (pinfunction "18_18") (pintype "passive"))
      (node (ref "MicroSD1") (pin "3") (pinfunction "CMD/RP_3") (pintype "power_in"))
      (node (ref "U1") (pin "55") (pinfunction "DBG_DO/SDC0_CMD/PF3_55") (pintype "passive"))
    )
    (net (code "31") (name "/HPCOM") (class "Default")
      (node (ref "C33") (pin "1") (pinfunction "1_1") (pintype "passive"))
      (node (ref "J1") (pin "2") (pinfunction "MIC_2") (pintype "passive"))
      (node (ref "R11") (pin "2") (pinfunction "2_2") (pintype "passive"))
      (node (ref "U1") (pin "3") (pinfunction "HPCOM_3") (pintype "passive"))
    )
    (net (code "32") (name "/HPCOMFB") (class "Default")
      (node (ref "R11") (pin "1") (pinfunction "1_1") (pintype "passive"))
      (node (ref "U1") (pin "2") (pinfunction "HPCOMFB_2") (pintype "passive"))
    )
    (net (code "33") (name "/HPL") (class "Default")
      (node (ref "C40") (pin "2") (pinfunction "2_2") (pintype "passive"))
      (node (ref "U1") (pin "1") (pinfunction "HPL_1") (pintype "passive"))
    )
    (net (code "34") (name "/HPR") (class "Default")
      (node (ref "C36") (pin "1") (pinfunction "1_1") (pintype "passive"))
      (node (ref "U1") (pin "88") (pinfunction "HPR_88") (pintype "passive"))
    )
    (net (code "35") (name "/LCD_CLK") (class "Default")
      (node (ref "CN1") (pin "30") (pinfunction "CLK_30") (pintype "passive"))
      (node (ref "U1") (pin "26") (pinfunction "PD18/LCD_CLK/SPI0_CS_26") (pintype "passive"))
    )
    (net (code "36") (name "/LCD_D2") (class "Default")
      (node (ref "CN1") (pin "7") (pinfunction "R2_7") (pintype "passive"))
      (node (ref "U1") (pin "6") (pinfunction "PD0/LCD_D2/TWI0_SDA_6") (pintype "passive"))
    )
    (net (code "37") (name "/LCD_D3") (class "Default")
      (node (ref "CN1") (pin "8") (pinfunction "R3_8") (pintype "passive"))
      (node (ref "U1") (pin "7") (pinfunction "PD1/LCD_D3/UART1_RTS_7") (pintype "passive"))
    )
    (net (code "38") (name "/LCD_D4") (class "Default")
      (node (ref "CN1") (pin "9") (pinfunction "R4_9") (pintype "passive"))
      (node (ref "U1") (pin "8") (pinfunction "PD2/LCD_D4/UART1_CTS_8") (pintype "passive"))
    )
    (net (code "39") (name "/LCD_D5") (class "Default")
      (node (ref "CN1") (pin "10") (pinfunction "R5_10") (pintype "passive"))
      (node (ref "U1") (pin "9") (pinfunction "PD3/LCD_D5/UART1_RX_9") (pintype "passive"))
    )
    (net (code "40") (name "/LCD_D6") (class "Default")
      (node (ref "CN1") (pin "11") (pinfunction "R6_11") (pintype "passive"))
      (node (ref "U1") (pin "10") (pinfunction "PD4/LCD_D6/UART1_TX_10") (pintype "passive"))
    )
    (net (code "41") (name "/LCD_D7") (class "Default")
      (node (ref "CN1") (pin "12") (pinfunction "R7_12") (pintype "passive"))
      (node (ref "U1") (pin "11") (pinfunction "PD5/LCD_D7/TWI1_SCK_11") (pintype "passive"))
    )
    (net (code "42") (name "/LCD_D10") (class "Default")
      (node (ref "CN1") (pin "15") (pinfunction "G2_15") (pintype "passive"))
      (node (ref "U1") (pin "12") (pinfunction "PD6/LCD_D10/TWI1_SDA_12") (pintype "passive"))
    )
    (net (code "43") (name "/LCD_D11") (class "Default")
      (node (ref "CN1") (pin "16") (pinfunction "G3_16") (pintype "passive"))
      (node (ref "U1") (pin "13") (pinfunction "PD7/LCD_D11/DA_MCLK_13") (pintype "passive"))
    )
    (net (code "44") (name "/LCD_D12") (class "Default")
      (node (ref "CN1") (pin "17") (pinfunction "G4_17") (pintype "passive"))
      (node (ref "U1") (pin "14") (pinfunction "PD8/LCD_D12/DA_BCLK_14") (pintype "passive"))
    )
    (net (code "45") (name "/LCD_D13") (class "Default")
      (node (ref "CN1") (pin "18") (pinfunction "G5_18") (pintype "passive"))
      (node (ref "U1") (pin "15") (pinfunction "PD9/LCD_D13/DA_LRCK_15") (pintype "passive"))
    )
    (net (code "46") (name "/LCD_D14") (class "Default")
      (node (ref "CN1") (pin "19") (pinfunction "G6_19") (pintype "passive"))
      (node (ref "U1") (pin "16") (pinfunction "PD10/LCD_D14/DA_IN_16") (pintype "passive"))
    )
    (net (code "47") (name "/LCD_D15") (class "Default")
      (node (ref "CN1") (pin "20") (pinfunction "G7_20") (pintype "passive"))
      (node (ref "U1") (pin "17") (pinfunction "PD11/LCD_D15/DA_OUT_17") (pintype "passive"))
    )
    (net (code "48") (name "/LCD_D18") (class "Default")
      (node (ref "CN1") (pin "23") (pinfunction "B2_23") (pintype "passive"))
      (node (ref "U1") (pin "18") (pinfunction "PD12/LCD_D18/TWI0_SCK_18") (pintype "passive"))
    )
    (net (code "49") (name "/LCD_D19") (class "Default")
      (node (ref "CN1") (pin "24") (pinfunction "B3_24") (pintype "passive"))
      (node (ref "U1") (pin "19") (pinfunction "PD13/LCD_D19/UART2_TX_19") (pintype "passive"))
    )
    (net (code "50") (name "/LCD_D20") (class "Default")
      (node (ref "CN1") (pin "25") (pinfunction "B4_25") (pintype "passive"))
      (node (ref "U1") (pin "21") (pinfunction "PD14/LCD_D20/UART2_RX_21") (pintype "passive"))
    )
    (net (code "51") (name "/LCD_D21") (class "Default")
      (node (ref "CN1") (pin "26") (pinfunction "B5_26") (pintype "passive"))
      (node (ref "U1") (pin "23") (pinfunction "PD15/LCD_D21/UART2_RTS/TWI2_SCK_23") (pintype "passive"))
    )
    (net (code "52") (name "/LCD_D22") (class "Default")
      (node (ref "CN1") (pin "27") (pinfunction "B6_27") (pintype "passive"))
      (node (ref "U1") (pin "24") (pinfunction "PD16/LCD_D22/UART2_CTS/TWI2_SDA_24") (pintype "passive"))
    )
    (net (code "53") (name "/LCD_D23") (class "Default")
      (node (ref "CN1") (pin "28") (pinfunction "B7_28") (pintype "passive"))
      (node (ref "U1") (pin "25") (pinfunction "PD17/LCD_D23/OWA_OUT_25") (pintype "passive"))
    )
    (net (code "54") (name "/LCD_DE") (class "Default")
      (node (ref "CN1") (pin "34") (pinfunction "DEN_34") (pintype "passive"))
      (node (ref "U1") (pin "27") (pinfunction "PD19/LCD_DE/SPI0_MOSI_27") (pintype "passive"))
    )
    (net (code "55") (name "/LCD_HSYNC") (class "Default")
      (node (ref "CN1") (pin "32") (pinfunction "HSYNC_32") (pintype "passive"))
      (node (ref "U1") (pin "28") (pinfunction "PD20/LCD_HSYNC/SPI0_CLK_28") (pintype "passive"))
    )
    (net (code "56") (name "/LCD_VSYNC") (class "Default")
      (node (ref "CN1") (pin "33") (pinfunction "VSYNC_33") (pintype "passive"))
      (node (ref "U1") (pin "29") (pinfunction "PD21/LCD_VSYNC/SPI0_MISO_29") (pintype "passive"))
    )
    (net (code "57") (name "/LEDA") (class "Default")
      (node (ref "C30") (pin "1") (pinfunction "1_1") (pintype "passive"))
      (node (ref "CN1") (pin "2") (pinfunction "LEDA_2") (pintype "passive"))
      (node (ref "D1") (pin "2") (pinfunction "K_2") (pintype "passive"))
      (node (ref "U6") (pin "5") (pinfunction "OUT_5") (pintype "passive"))
    )
    (net (code "58") (name "/LEDK") (class "Default")
      (node (ref "CN1") (pin "1") (pinfunction "LEDK_1") (pintype "passive"))
      (node (ref "R16") (pin "2") (pinfunction "2_2") (pintype "passive"))
      (node (ref "U6") (pin "3") (pinfunction "FB_3") (pintype "passive"))
    )
    (net (code "59") (name "/LINE_IN") (class "Default")
      (node (ref "T6") (pin "1") (pintype "passive"))
      (node (ref "U1") (pin "86") (pinfunction "LINE_IN_86") (pintype "passive"))
    )
    (net (code "60") (name "/LRADC") (class "Default")
      (node (ref "J2") (pin "22") (pinfunction "22_22") (pintype "passive"))
      (node (ref "U1") (pin "79") (pinfunction "LRADC0_79") (pintype "passive"))
    )
    (net (code "61") (name "/MIC_IN") (class "Default")
      (node (ref "J1") (pin "3") (pinfunction "GND_3") (pintype "passive"))
      (node (ref "U1") (pin "87") (pinfunction "MIC_IN_87") (pintype "passive"))
    )
    (net (code "62") (name "/RST_N") (class "Default")
      (node (ref "C18") (pin "2") (pinfunction "2_2") (pintype "passive"))
      (node (ref "R9") (pin "1") (pinfunction "1_1") (pintype "passive"))
      (node (ref "U1") (pin "70") (pinfunction "RST_N_70") (pintype "passive"))
    )
    (net (code "63") (name "/SD_Dectec") (class "Default")
      (node (ref "MicroSD1") (pin "9") (pinfunction "SD_9") (pintype "power_in"))
    )
    (net (code "64") (name "/SVREF") (class "Default")
      (node (ref "C38") (pin "1") (pinfunction "1_1") (pintype "passive"))
      (node (ref "C39") (pin "2") (pinfunction "2_2") (pintype "passive"))
      (node (ref "R17") (pin "1") (pinfunction "1_1") (pintype "passive"))
      (node (ref "R18") (pin "2") (pinfunction "2_2") (pintype "passive"))
      (node (ref "U1") (pin "33") (pinfunction "SVREF_33") (pintype "passive"))
    )
    (net (code "65") (name "/TV_IN0") (class "Default")
      (node (ref "C37") (pin "1") (pinfunction "1_1") (pintype "passive"))
      (node (ref "U1") (pin "78") (pinfunction "TV_IN0_78") (pintype "passive"))
    )
    (net (code "66") (name "/TV_IN1") (class "Default")
      (node (ref "T1") (pin "1") (pintype "passive"))
      (node (ref "U1") (pin "77") (pinfunction "TV_IN1_77") (pintype "passive"))
    )
    (net (code "67") (name "/TV_INPUT") (class "Default")
      (node (ref "C34") (pin "2") (pinfunction "2_2") (pintype "passive"))
      (node (ref "C41") (pin "1") (pinfunction "1_1") (pintype "passive"))
      (node (ref "FB1") (pin "1") (pinfunction "1_1") (pintype "passive"))
      (node (ref "R15") (pin "2") (pinfunction "2_2") (pintype "passive"))
      (node (ref "T3") (pin "1") (pintype "passive"))
    )
    (net (code "68") (name "/TV_OUT") (class "Default")
      (node (ref "T2") (pin "1") (pintype "passive"))
      (node (ref "U1") (pin "72") (pinfunction "TV_OUT_72") (pintype "passive"))
    )
    (net (code "69") (name "/TV_VRN") (class "Default")
      (node (ref "C10") (pin "1") (pinfunction "1_1") (pintype "passive"))
      (node (ref "C15") (pin "1") (pinfunction "1_1") (pintype "passive"))
      (node (ref "U1") (pin "75") (pinfunction "TV_VRN_75") (pintype "passive"))
    )
    (net (code "70") (name "/TV_VRP") (class "Default")
      (node (ref "C10") (pin "2") (pinfunction "2_2") (pintype "passive"))
      (node (ref "C7") (pin "1") (pinfunction "1_1") (pintype "passive"))
      (node (ref "U1") (pin "76") (pinfunction "TV_VRP_76") (pintype "passive"))
    )
    (net (code "71") (name "/USB_DM") (class "Default")
      (node (ref "U1") (pin "68") (pinfunction "USB_DM_68") (pintype "passive"))
      (node (ref "USBC1") (pin "A7") (pinfunction "DN1_A7") (pintype "passive"))
      (node (ref "USBC1") (pin "B7") (pinfunction "DN2_B7") (pintype "passive"))
    )
    (net (code "72") (name "/USB_DP") (class "Default")
      (node (ref "U1") (pin "69") (pinfunction "USB_DP_69") (pintype "passive"))
      (node (ref "USBC1") (pin "A6") (pinfunction "DP1_A6") (pintype "passive"))
      (node (ref "USBC1") (pin "B6") (pinfunction "DP2_B6") (pintype "passive"))
    )
    (net (code "73") (name "/VRA1") (class "Default")
      (node (ref "C6") (pin "1") (pinfunction "1_1") (pintype "passive"))
      (node (ref "R2") (pin "2") (pinfunction "2_2") (pintype "passive"))
      (node (ref "U1") (pin "81") (pinfunction "VRA1_81") (pintype "passive"))
    )
    (net (code "74") (name "/VRA2") (class "Default")
      (node (ref "C1") (pin "1") (pinfunction "1_1") (pintype "passive"))
      (node (ref "R1") (pin "2") (pinfunction "2_2") (pintype "passive"))
      (node (ref "U1") (pin "83") (pinfunction "VRA2_83") (pintype "passive"))
    )
    (net (code "75") (name "AGND") (class "Default")
      (node (ref "C1") (pin "2") (pinfunction "2_2") (pintype "passive"))
      (node (ref "C12") (pin "1") (pinfunction "1_1") (pintype "passive"))
      (node (ref "C13") (pin "1") (pinfunction "1_1") (pintype "passive"))
      (node (ref "C14") (pin "1") (pinfunction "1_1") (pintype "passive"))
      (node (ref "C15") (pin "2") (pinfunction "2_2") (pintype "passive"))
      (node (ref "C16") (pin "1") (pinfunction "1_1") (pintype "passive"))
      (node (ref "C17") (pin "1") (pinfunction "1_1") (pintype "passive"))
      (node (ref "C18") (pin "1") (pinfunction "1_1") (pintype "passive"))
      (node (ref "C19") (pin "1") (pinfunction "1_1") (pintype "passive"))
      (node (ref "C2") (pin "1") (pinfunction "1_1") (pintype "passive"))
      (node (ref "C20") (pin "1") (pinfunction "1_1") (pintype "passive"))
      (node (ref "C21") (pin "1") (pinfunction "1_1") (pintype "passive"))
      (node (ref "C22") (pin "1") (pinfunction "1_1") (pintype "passive"))
      (node (ref "C23") (pin "1") (pinfunction "1_1") (pintype "passive"))
      (node (ref "C24") (pin "1") (pinfunction "1_1") (pintype "passive"))
      (node (ref "C25") (pin "2") (pinfunction "2_2") (pintype "passive"))
      (node (ref "C26") (pin "1") (pinfunction "1_1") (pintype "passive"))
      (node (ref "C27") (pin "1") (pinfunction "1_1") (pintype "passive"))
      (node (ref "C28") (pin "1") (pinfunction "1_1") (pintype "passive"))
      (node (ref "C29") (pin "1") (pinfunction "1_1") (pintype "passive"))
      (node (ref "C3") (pin "1") (pinfunction "1_1") (pintype "passive"))
      (node (ref "C30") (pin "2") (pinfunction "2_2") (pintype "passive"))
      (node (ref "C31") (pin "1") (pinfunction "1_1") (pintype "passive"))
      (node (ref "C32") (pin "1") (pinfunction "1_1") (pintype "passive"))
      (node (ref "C35") (pin "1") (pinfunction "1_1") (pintype "passive"))
      (node (ref "C39") (pin "1") (pinfunction "1_1") (pintype "passive"))
      (node (ref "C4") (pin "2") (pinfunction "2_2") (pintype "passive"))
      (node (ref "C41") (pin "2") (pinfunction "2_2") (pintype "passive"))
      (node (ref "C42") (pin "2") (pinfunction "2_2") (pintype "passive"))
      (node (ref "C43") (pin "1") (pinfunction "1_1") (pintype "passive"))
      (node (ref "C44") (pin "1") (pinfunction "1_1") (pintype "passive"))
      (node (ref "C45") (pin "2") (pinfunction "2_2") (pintype "passive"))
      (node (ref "C46") (pin "1") (pinfunction "1_1") (pintype "passive"))
      (node (ref "C47") (pin "1") (pinfunction "1_1") (pintype "passive"))
      (node (ref "C6") (pin "2") (pinfunction "2_2") (pintype "passive"))
      (node (ref "C7") (pin "2") (pinfunction "2_2") (pintype "passive"))
      (node (ref "C9") (pin "2") (pinfunction "2_2") (pintype "passive"))
      (node (ref "CN1") (pin "13") (pinfunction "G0_13") (pintype "passive"))
      (node (ref "CN1") (pin "14") (pinfunction "G1_14") (pintype "passive"))
      (node (ref "CN1") (pin "21") (pinfunction "B0_21") (pintype "passive"))
      (node (ref "CN1") (pin "22") (pinfunction "B1_22") (pintype "passive"))
      (node (ref "CN1") (pin "29") (pinfunction "GND_29") (pintype "passive"))
      (node (ref "CN1") (pin "3") (pinfunction "GND_3") (pintype "passive"))
      (node (ref "CN1") (pin "36") (pinfunction "GND_36") (pintype "passive"))
      (node (ref "CN1") (pin "41") (pinfunction "GND_41") (pintype "passive"))
      (node (ref "CN1") (pin "42") (pinfunction "GND_42") (pintype "passive"))
      (node (ref "CN1") (pin "5") (pinfunction "R0_5") (pintype "passive"))
      (node (ref "CN1") (pin "6") (pinfunction "R1_6") (pintype "passive"))
      (node (ref "CN2") (pin "10") (pinfunction "10_10") (pintype "passive"))
      (node (ref "CN2") (pin "23") (pinfunction "23_23") (pintype "passive"))
      (node (ref "DS1") (pin "2") (pinfunction "K_2") (pintype "passive"))
      (node (ref "J2") (pin "13") (pinfunction "13_13") (pintype "passive"))
      (node (ref "J2") (pin "14") (pinfunction "14_14") (pintype "passive"))
      (node (ref "J2") (pin "21") (pinfunction "21_21") (pintype "passive"))
      (node (ref "J2") (pin "24") (pinfunction "24_24") (pintype "passive"))
      (node (ref "J2") (pin "3") (pinfunction "3_3") (pintype "passive"))
      (node (ref "J2") (pin "37") (pinfunction "37_37") (pintype "passive"))
      (node (ref "J2") (pin "38") (pinfunction "38_38") (pintype "passive"))
      (node (ref "J2") (pin "4") (pinfunction "4_4") (pintype "passive"))
      (node (ref "J3") (pin "3") (pinfunction "3_3") (pintype "passive"))
      (node (ref "MicroSD1") (pin "10") (pinfunction "PAD1_10") (pintype "power_in"))
      (node (ref "MicroSD1") (pin "11") (pinfunction "PAD2_11") (pintype "power_in"))
      (node (ref "MicroSD1") (pin "12") (pinfunction "PAD3_12") (pintype "power_in"))
      (node (ref "MicroSD1") (pin "13") (pinfunction "PAD4_13") (pintype "power_in"))
      (node (ref "MicroSD1") (pin "6") (pinfunction "VSS_6") (pintype "power_in"))
      (node (ref "R1") (pin "1") (pinfunction "1_1") (pintype "passive"))
      (node (ref "R12") (pin "2") (pinfunction "2_2") (pintype "passive"))
      (node (ref "R15") (pin "1") (pinfunction "1_1") (pintype "passive"))
      (node (ref "R16") (pin "1") (pinfunction "1_1") (pintype "passive"))
      (node (ref "R18") (pin "1") (pinfunction "1_1") (pintype "passive"))
      (node (ref "R19") (pin "1") (pinfunction "1_1") (pintype "passive"))
      (node (ref "R2") (pin "1") (pinfunction "1_1") (pintype "passive"))
      (node (ref "R4") (pin "2") (pinfunction "2_2") (pintype "passive"))
      (node (ref "R5") (pin "2") (pinfunction "2_2") (pintype "passive"))
      (node (ref "R7") (pin "2") (pinfunction "2_2") (pintype "passive"))
      (node (ref "S1") (pin "2") (pinfunction "2_2") (pintype "passive"))
      (node (ref "U1") (pin "74") (pinfunction "TV_GND_74") (pintype "passive"))
      (node (ref "U1") (pin "82") (pinfunction "AGND_82") (pintype "passive"))
      (node (ref "U1") (pin "89") (pinfunction "EPAD_89") (pintype "passive"))
      (node (ref "U2") (pin "1") (pinfunction "GND_1") (pintype "power_in"))
      (node (ref "U3") (pin "1") (pinfunction "GND3_1") (pintype "passive"))
      (node (ref "U3") (pin "12") (pinfunction "GND1_12") (pintype "passive"))
      (node (ref "U3") (pin "13") (pinfunction "GND1_13") (pintype "passive"))
      (node (ref "U3") (pin "15") (pinfunction "AGND_15") (pintype "passive"))
      (node (ref "U3") (pin "17") (pinfunction "AGND_17") (pintype "passive"))
      (node (ref "U3") (pin "21") (pinfunction "EP_21") (pintype "passive"))
      (node (ref "U3") (pin "4") (pinfunction "GND2_4") (pintype "passive"))
      (node (ref "U3") (pin "5") (pinfunction "GND2_5") (pintype "passive"))
      (node (ref "U4") (pin "1") (pinfunction "GND_1") (pintype "power_in"))
      (node (ref "U5") (pin "1") (pinfunction "GND_1") (pintype "power_in"))
      (node (ref "U6") (pin "2") (pinfunction "GND_2") (pintype "passive"))
      (node (ref "U7") (pin "4") (pinfunction "GND_4") (pintype "power_in"))
      (node (ref "U8") (pin "13") (pinfunction "GND_13") (pintype "passive"))
      (node (ref "U8") (pin "2") (pinfunction "GND_2") (pintype "passive"))
      (node (ref "U8") (pin "3") (pinfunction "LED-_3") (pintype "passive"))
      (node (ref "U8") (pin "5") (pinfunction "GND_5") (pintype "passive"))
      (node (ref "USBC1") (pin "0") (pinfunction "0_0") (pintype "passive"))
      (node (ref "USBC1") (pin "A1") (pinfunction "GND_A1") (pintype "passive"))
      (node (ref "USBC1") (pin "A12") (pinfunction "GND_A12") (pintype "passive"))
      (node (ref "USBC1") (pin "B1") (pinfunction "GND_B1") (pintype "passive"))
      (node (ref "USBC1") (pin "B12") (pinfunction "GND_B12") (pintype "passive"))
      (node (ref "X1") (pin "2") (pintype "power_in"))
      (node (ref "X1") (pin "4") (pintype "passive"))
    )
    (net (code "76") (name "AVCC") (class "Default")
      (node (ref "C13") (pin "2") (pinfunction "2_2") (pintype "passive"))
      (node (ref "C24") (pin "2") (pinfunction "2_2") (pintype "passive"))
      (node (ref "U1") (pin "80") (pinfunction "AVCC_80") (pintype "passive"))
      (node (ref "U4") (pin "2") (pinfunction "VOUT_2") (pintype "power_in"))
    )
    (net (code "77") (name "CSI_DVDD") (class "Default")
      (node (ref "C17") (pin "2") (pinfunction "2_2") (pintype "passive"))
      (node (ref "CN2") (pin "15") (pinfunction "15_15") (pintype "passive"))
      (node (ref "JP1") (pin "1") (pintype "power_in"))
      (node (ref "U5") (pin "2") (pinfunction "VOUT_2") (pintype "power_in"))
    )
    (net (code "78") (name "Net-(C33-Pad2)") (class "Default")
      (node (ref "C33") (pin "2") (pinfunction "2_2") (pintype "passive"))
      (node (ref "R12") (pin "1") (pinfunction "1_1") (pintype "passive"))
    )
    (net (code "79") (name "Net-(C34-Pad1)") (class "Default")
      (node (ref "C34") (pin "1") (pinfunction "1_1") (pintype "passive"))
      (node (ref "C37") (pin "2") (pinfunction "2_2") (pintype "passive"))
      (node (ref "C42") (pin "1") (pinfunction "1_1") (pintype "passive"))
      (node (ref "FB1") (pin "2") (pinfunction "2_2") (pintype "passive"))
    )
    (net (code "80") (name "Net-(D1-A)") (class "Default")
      (node (ref "D1") (pin "1") (pinfunction "A_1") (pintype "passive"))
      (node (ref "L4") (pin "2") (pinfunction "2_2") (pintype "passive"))
      (node (ref "U6") (pin "1") (pinfunction "SW_1") (pintype "passive"))
    )
    (net (code "81") (name "Net-(DS1-A)") (class "Default")
      (node (ref "DS1") (pin "1") (pinfunction "A_1") (pintype "passive"))
      (node (ref "R23") (pin "1") (pinfunction "1_1") (pintype "passive"))
    )
    (net (code "82") (name "Net-(DS2-A)") (class "Default")
      (node (ref "DS2") (pin "1") (pinfunction "A_1") (pintype "passive"))
      (node (ref "R24") (pin "1") (pinfunction "1_1") (pintype "passive"))
    )
    (net (code "83") (name "Net-(J1-L)") (class "Default")
      (node (ref "C40") (pin "1") (pinfunction "1_1") (pintype "passive"))
      (node (ref "J1") (pin "6") (pinfunction "L_6") (pintype "passive"))
    )
    (net (code "84") (name "Net-(J1-R)") (class "Default")
      (node (ref "C36") (pin "2") (pinfunction "2_2") (pintype "passive"))
      (node (ref "J1") (pin "4") (pinfunction "R_4") (pintype "passive"))
    )
    (net (code "85") (name "Net-(U1-HOSCI)") (class "Default")
      (node (ref "C35") (pin "2") (pinfunction "2_2") (pintype "passive"))
      (node (ref "U1") (pin "51") (pinfunction "HOSCI_51") (pintype "passive"))
      (node (ref "X1") (pin "1") (pintype "power_in"))
    )
    (net (code "86") (name "Net-(U1-HOSC_OUT)") (class "Default")
      (node (ref "C31") (pin "2") (pinfunction "2_2") (pintype "passive"))
      (node (ref "U1") (pin "52") (pinfunction "HOSC_OUT_52") (pintype "passive"))
      (node (ref "X1") (pin "3") (pinfunction "GND_3") (pintype "power_in"))
    )
    (net (code "87") (name "Net-(U3-FB1)") (class "Default")
      (node (ref "C8") (pin "2") (pinfunction "2_2") (pintype "passive"))
      (node (ref "R4") (pin "1") (pinfunction "1_1") (pintype "passive"))
      (node (ref "R6") (pin "1") (pinfunction "1_1") (pintype "passive"))
      (node (ref "U3") (pin "14") (pinfunction "FB1_14") (pintype "passive"))
    )
    (net (code "88") (name "Net-(U3-FB2)") (class "Default")
      (node (ref "C11") (pin "2") (pinfunction "2_2") (pintype "passive"))
      (node (ref "R7") (pin "1") (pinfunction "1_1") (pintype "passive"))
      (node (ref "R8") (pin "2") (pinfunction "2_2") (pintype "passive"))
      (node (ref "U3") (pin "3") (pinfunction "FB2_3") (pintype "passive"))
    )
    (net (code "89") (name "Net-(U3-FB3)") (class "Default")
      (node (ref "C5") (pin "2") (pinfunction "2_2") (pintype "passive"))
      (node (ref "R3") (pin "1") (pinfunction "1_1") (pintype "passive"))
      (node (ref "R5") (pin "1") (pinfunction "1_1") (pintype "passive"))
      (node (ref "U3") (pin "2") (pinfunction "FB3_2") (pintype "passive"))
    )
    (net (code "90") (name "Net-(U3-LX1)") (class "Default")
      (node (ref "L2") (pin "1") (pinfunction "1_1") (pintype "passive"))
      (node (ref "U3") (pin "11") (pinfunction "LX1_11") (pintype "passive"))
    )
    (net (code "91") (name "Net-(U3-LX2)") (class "Default")
      (node (ref "L3") (pin "2") (pinfunction "2_2") (pintype "passive"))
      (node (ref "U3") (pin "6") (pinfunction "LX2_6") (pintype "passive"))
    )
    (net (code "92") (name "Net-(U3-LX3)") (class "Default")
      (node (ref "L1") (pin "2") (pinfunction "2_2") (pintype "passive"))
      (node (ref "U3") (pin "20") (pinfunction "LX3_20") (pintype "passive"))
    )
    (net (code "93") (name "Net-(U6-EN)") (class "Default")
      (node (ref "R13") (pin "2") (pinfunction "2_2") (pintype "passive"))
      (node (ref "R14") (pin "2") (pinfunction "2_2") (pintype "passive"))
      (node (ref "U6") (pin "4") (pinfunction "EN_4") (pintype "passive"))
    )
    (net (code "94") (name "Net-(U8-LED+)") (class "Default")
      (node (ref "R22") (pin "2") (pinfunction "2_2") (pintype "passive"))
      (node (ref "U8") (pin "4") (pinfunction "LED+_4") (pintype "passive"))
    )
    (net (code "95") (name "Net-(U8-RST_N)") (class "Default")
      (node (ref "C45") (pin "1") (pinfunction "1_1") (pintype "passive"))
      (node (ref "R25") (pin "2") (pinfunction "2_2") (pintype "passive"))
      (node (ref "U8") (pin "6") (pinfunction "RST_N_6") (pintype "passive"))
    )
    (net (code "96") (name "Net-(USBC1-CC1)") (class "Default")
      (node (ref "J3") (pin "2") (pinfunction "2_2") (pintype "passive"))
      (node (ref "USBC1") (pin "A5") (pinfunction "CC1_A5") (pintype "passive"))
      (node (ref "USBC1") (pin "B5") (pinfunction "CC2_B5") (pintype "passive"))
    )
    (net (code "97") (name "VCC_1V1") (class "Default")
      (node (ref "C11") (pin "1") (pinfunction "1_1") (pintype "passive"))
      (node (ref "C14") (pin "2") (pinfunction "2_2") (pintype "passive"))
      (node (ref "C21") (pin "2") (pinfunction "2_2") (pintype "passive"))
      (node (ref "C22") (pin "2") (pinfunction "2_2") (pintype "passive"))
      (node (ref "C23") (pin "2") (pinfunction "2_2") (pintype "passive"))
      (node (ref "L3") (pin "1") (pinfunction "1_1") (pintype "passive"))
      (node (ref "R8") (pin "1") (pinfunction "1_1") (pintype "passive"))
      (node (ref "U1") (pin "22") (pinfunction "VDD_CORE_22") (pintype "passive"))
      (node (ref "U1") (pin "35") (pinfunction "VDD_CORE_35") (pintype "passive"))
      (node (ref "U1") (pin "71") (pinfunction "VDD_CORE_71") (pintype "passive"))
    )
    (net (code "98") (name "VCC_2V5") (class "Default")
      (node (ref "C19") (pin "2") (pinfunction "2_2") (pintype "passive"))
      (node (ref "C20") (pin "2") (pinfunction "2_2") (pintype "passive"))
      (node (ref "C38") (pin "2") (pinfunction "2_2") (pintype "passive"))
      (node (ref "C8") (pin "1") (pinfunction "1_1") (pintype "passive"))
      (node (ref "C9") (pin "1") (pinfunction "1_1") (pintype "passive"))
      (node (ref "L2") (pin "2") (pinfunction "2_2") (pintype "passive"))
      (node (ref "R17") (pin "2") (pinfunction "2_2") (pintype "passive"))
      (node (ref "R6") (pin "2") (pinfunction "2_2") (pintype "passive"))
      (node (ref "U1") (pin "30") (pinfunction "VCC_DRAM_30") (pintype "passive"))
      (node (ref "U1") (pin "31") (pinfunction "VCC_DRAM_31") (pintype "passive"))
      (node (ref "U1") (pin "32") (pinfunction "VCC_DRAM_32") (pintype "passive"))
      (node (ref "U1") (pin "34") (pinfunction "VCC_DRAM_34") (pintype "passive"))
      (node (ref "U1") (pin "36") (pinfunction "VCC_DRAM_36") (pintype "passive"))
    )
    (net (code "99") (name "VCC_2V8") (class "Default")
      (node (ref "C3") (pin "2") (pinfunction "2_2") (pintype "passive"))
      (node (ref "CN2") (pin "21") (pinfunction "21_21") (pintype "passive"))
      (node (ref "JP1") (pin "2") (pintype "power_in"))
      (node (ref "U2") (pin "2") (pinfunction "VOUT_2") (pintype "power_in"))
    )
    (net (code "100") (name "VCC_3V3") (class "Default")
      (node (ref "C12") (pin "2") (pinfunction "2_2") (pintype "passive"))
      (node (ref "C16") (pin "2") (pinfunction "2_2") (pintype "passive"))
      (node (ref "C2") (pin "2") (pinfunction "2_2") (pintype "passive"))
      (node (ref "C25") (pin "1") (pinfunction "1_1") (pintype "passive"))
      (node (ref "C26") (pin "2") (pinfunction "2_2") (pintype "passive"))
      (node (ref "C27") (pin "2") (pinfunction "2_2") (pintype "passive"))
      (node (ref "C28") (pin "2") (pinfunction "2_2") (pintype "passive"))
      (node (ref "C4") (pin "1") (pinfunction "1_1") (pintype "passive"))
      (node (ref "C43") (pin "2") (pinfunction "2_2") (pintype "passive"))
      (node (ref "C44") (pin "2") (pinfunction "2_2") (pintype "passive"))
      (node (ref "C5") (pin "1") (pinfunction "1_1") (pintype "passive"))
      (node (ref "CN1") (pin "31") (pinfunction "DISP_31") (pintype "passive"))
      (node (ref "CN1") (pin "4") (pinfunction "VCC_4") (pintype "passive"))
      (node (ref "CN2") (pin "14") (pinfunction "14_14") (pintype "passive"))
      (node (ref "J2") (pin "2") (pinfunction "2_2") (pintype "passive"))
      (node (ref "J2") (pin "39") (pinfunction "39_39") (pintype "passive"))
      (node (ref "L1") (pin "1") (pinfunction "1_1") (pintype "passive"))
      (node (ref "MicroSD1") (pin "4") (pinfunction "VDD_4") (pintype "power_in"))
      (node (ref "R10") (pin "2") (pinfunction "2_2") (pintype "passive"))
      (node (ref "R20") (pin "2") (pinfunction "2_2") (pintype "passive"))
      (node (ref "R21") (pin "2") (pinfunction "2_2") (pintype "passive"))
      (node (ref "R22") (pin "1") (pinfunction "1_1") (pintype "passive"))
      (node (ref "R24") (pin "2") (pinfunction "2_2") (pintype "passive"))
      (node (ref "R25") (pin "1") (pinfunction "1_1") (pintype "passive"))
      (node (ref "R3") (pin "2") (pinfunction "2_2") (pintype "passive"))
      (node (ref "R9") (pin "2") (pinfunction "2_2") (pintype "passive"))
      (node (ref "U1") (pin "20") (pinfunction "VCC_IO_20") (pintype "passive"))
      (node (ref "U1") (pin "4") (pinfunction "HPVCC_4") (pintype "passive"))
      (node (ref "U1") (pin "5") (pinfunction "VCC_IO_5") (pintype "passive"))
      (node (ref "U1") (pin "50") (pinfunction "VCC_IO_50") (pintype "passive"))
      (node (ref "U1") (pin "67") (pinfunction "VCC_USB_67") (pintype "passive"))
      (node (ref "U2") (pin "3") (pinfunction "VIN_3") (pintype "power_in"))
      (node (ref "U4") (pin "3") (pinfunction "VIN_3") (pintype "power_in"))
      (node (ref "U5") (pin "3") (pinfunction "VIN_3") (pintype "power_in"))
      (node (ref "U7") (pin "3") (pinfunction "WP_3") (pintype "power_in"))
      (node (ref "U7") (pin "7") (pinfunction "Hold_7") (pintype "power_in"))
      (node (ref "U7") (pin "8") (pinfunction "VCC_8") (pintype "power_in"))
      (node (ref "U8") (pin "10") (pinfunction "VCC_10") (pintype "passive"))
      (node (ref "U8") (pin "11") (pinfunction "IOVCC_11") (pintype "passive"))
    )
    (net (code "101") (name "VCC_TV") (class "Default")
      (node (ref "C29") (pin "2") (pinfunction "2_2") (pintype "passive"))
      (node (ref "R10") (pin "1") (pinfunction "1_1") (pintype "passive"))
      (node (ref "U1") (pin "73") (pinfunction "TV_VCC_73") (pintype "passive"))
    )
    (net (code "102") (name "unconnected-(CN1-NC-Pad35)") (class "Default")
      (node (ref "CN1") (pin "35") (pinfunction "NC_35") (pintype "passive+no_connect"))
    )
    (net (code "103") (name "unconnected-(CN2-Pad1)") (class "Default")
      (node (ref "CN2") (pin "1") (pinfunction "1_1") (pintype "passive+no_connect"))
    )
    (net (code "104") (name "unconnected-(CN2-Pad2)") (class "Default")
      (node (ref "CN2") (pin "2") (pinfunction "2_2") (pintype "passive+no_connect"))
    )
    (net (code "105") (name "unconnected-(CN2-Pad24)") (class "Default")
      (node (ref "CN2") (pin "24") (pinfunction "24_24") (pintype "passive+no_connect"))
    )
    (net (code "106") (name "unconnected-(J1-L_DET-Pad7)") (class "Default")
      (node (ref "J1") (pin "7") (pinfunction "L_DET_7") (pintype "passive"))
    )
    (net (code "107") (name "unconnected-(J1-R_DET-Pad5)") (class "Default")
      (node (ref "J1") (pin "5") (pinfunction "R_DET_5") (pintype "passive"))
    )
    (net (code "108") (name "unconnected-(U8-NC-Pad1)") (class "Default")
      (node (ref "U8") (pin "1") (pinfunction "NC_1") (pintype "passive"))
    )
    (net (code "109") (name "unconnected-(U8-NC-Pad14)") (class "Default")
      (node (ref "U8") (pin "14") (pinfunction "NC_14") (pintype "passive"))
    )
    (net (code "110") (name "unconnected-(USBC1-SBU1-PadA8)") (class "Default")
      (node (ref "USBC1") (pin "A8") (pinfunction "SBU1_A8") (pintype "passive"))
    )
    (net (code "111") (name "unconnected-(USBC1-SBU2-PadB8)") (class "Default")
      (node (ref "USBC1") (pin "B8") (pinfunction "SBU2_B8") (pintype "passive"))
    )
  )
)
